# display_board.net
KiCad netlist of a schematic drawn in EAGLE
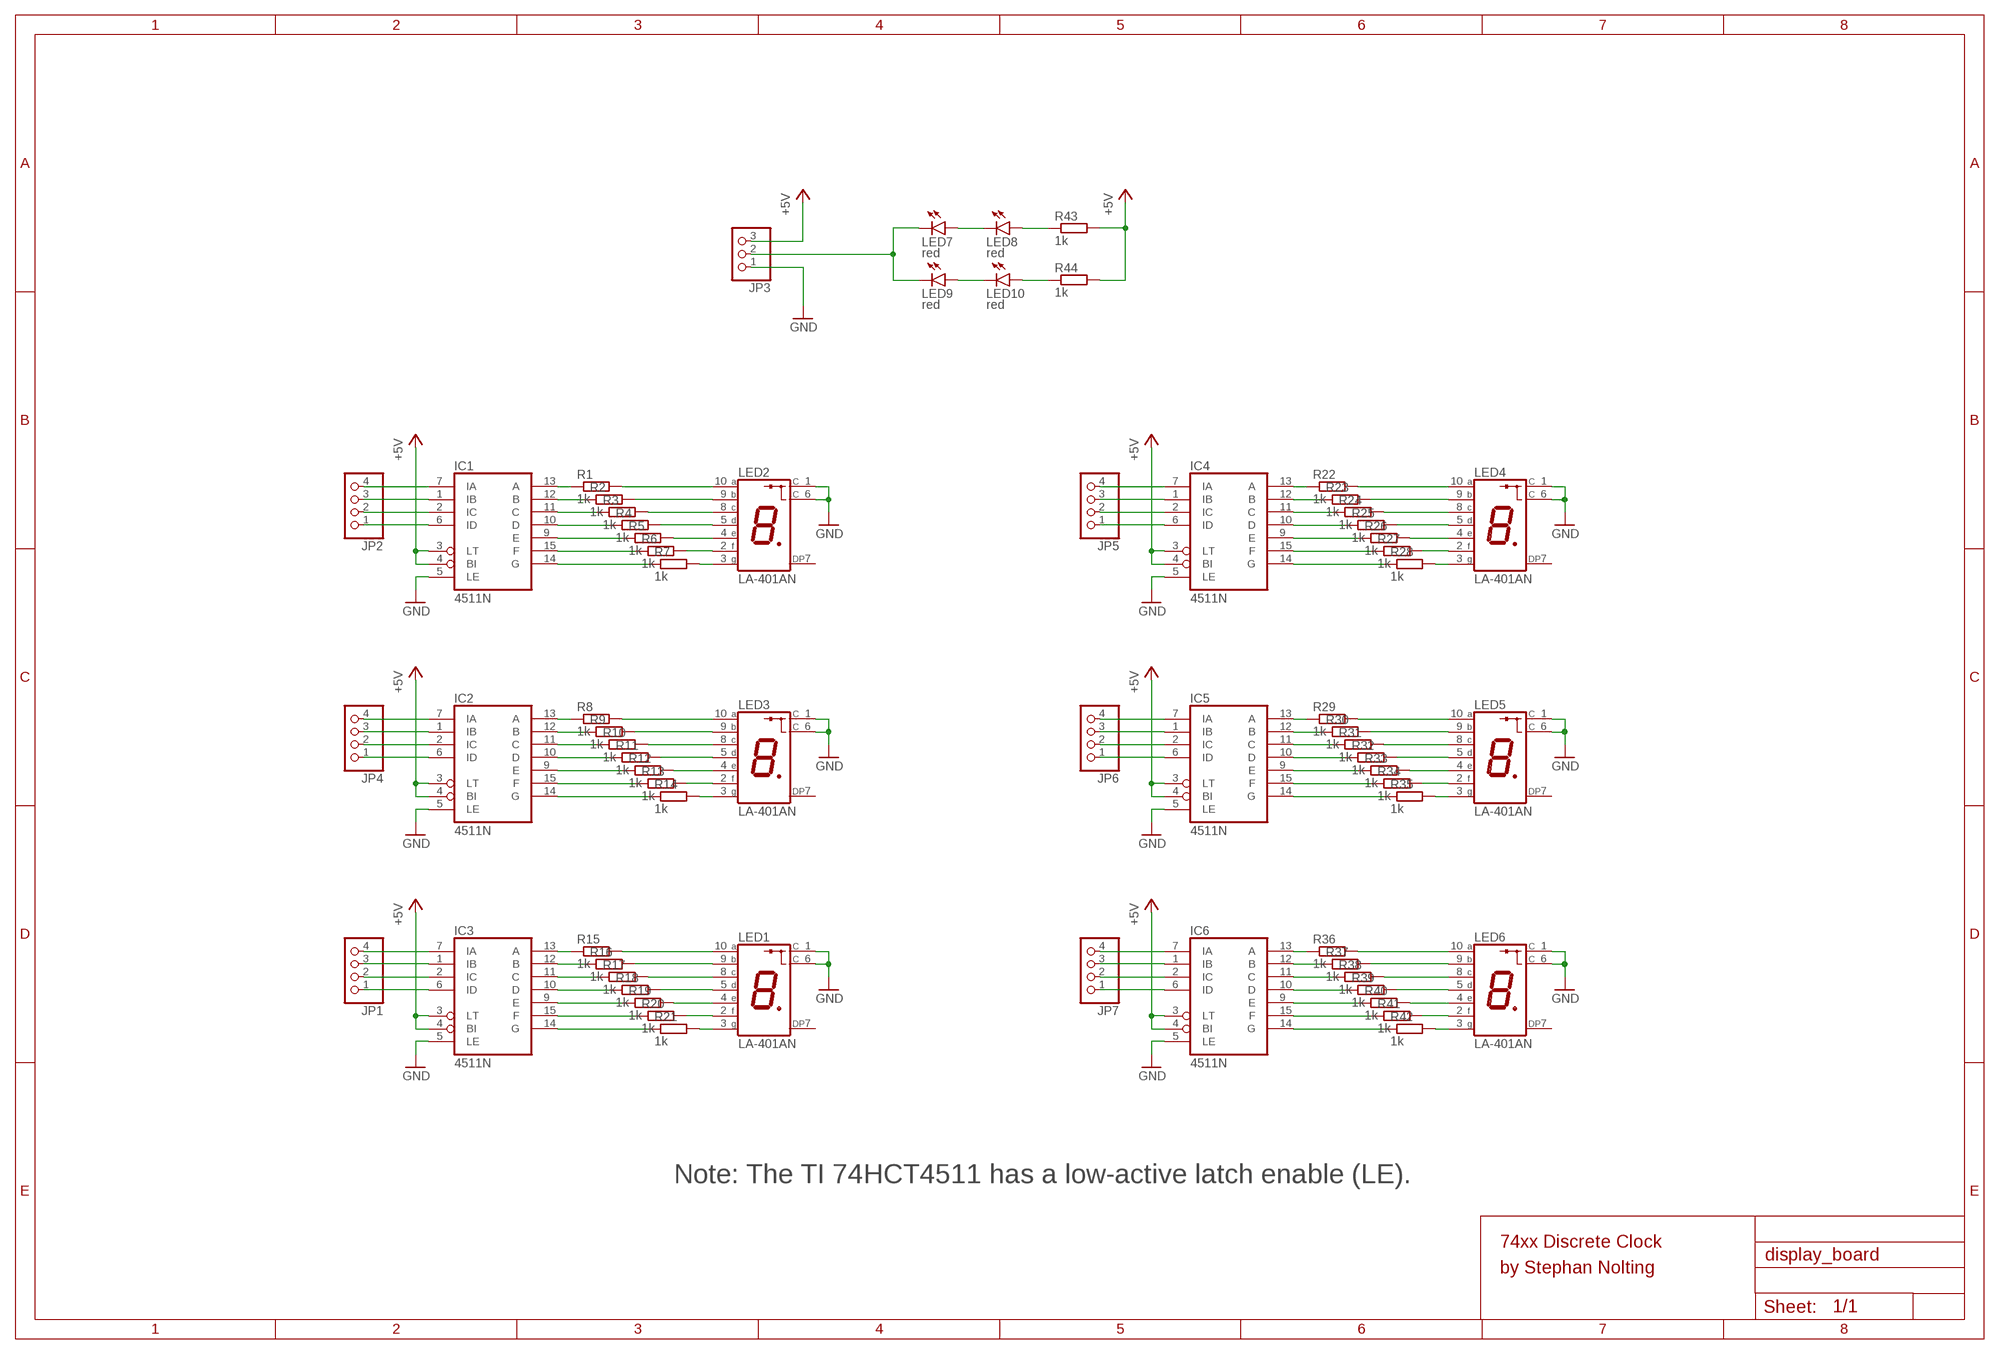
[diagram p0: schematic, sheet 1]

(export (version "E")
  (design (tool "Eeschema 10.0.6"))
  (components
    (comp (ref "IC1")
      (value "4511N")
      (footprint "eagle-import:DIL16")
      (libsource (lib "eagle-import") (part "4511N"))
    )
    (comp (ref "IC2")
      (value "4511N")
      (footprint "eagle-import:DIL16")
      (libsource (lib "eagle-import") (part "4511N"))
    )
    (comp (ref "IC3")
      (value "4511N")
      (footprint "eagle-import:DIL16")
      (libsource (lib "eagle-import") (part "4511N"))
    )
    (comp (ref "IC4")
      (value "4511N")
      (footprint "eagle-import:DIL16")
      (libsource (lib "eagle-import") (part "4511N"))
    )
    (comp (ref "IC5")
      (value "4511N")
      (footprint "eagle-import:DIL16")
      (libsource (lib "eagle-import") (part "4511N"))
    )
    (comp (ref "IC6")
      (value "4511N")
      (footprint "eagle-import:DIL16")
      (libsource (lib "eagle-import") (part "4511N"))
    )
    (comp (ref "JP1")
      (value "PINHD-1X4")
      (footprint "eagle-import:1X04")
      (libsource (lib "eagle-import") (part "PINHD-1X4"))
    )
    (comp (ref "JP2")
      (value "PINHD-1X4")
      (footprint "eagle-import:1X04")
      (libsource (lib "eagle-import") (part "PINHD-1X4"))
    )
    (comp (ref "JP3")
      (value "PINHD-1X3")
      (footprint "eagle-import:1X03")
      (libsource (lib "eagle-import") (part "PINHD-1X3"))
    )
    (comp (ref "JP4")
      (value "PINHD-1X4")
      (footprint "eagle-import:1X04")
      (libsource (lib "eagle-import") (part "PINHD-1X4"))
    )
    (comp (ref "JP5")
      (value "PINHD-1X4")
      (footprint "eagle-import:1X04")
      (libsource (lib "eagle-import") (part "PINHD-1X4"))
    )
    (comp (ref "JP6")
      (value "PINHD-1X4")
      (footprint "eagle-import:1X04")
      (libsource (lib "eagle-import") (part "PINHD-1X4"))
    )
    (comp (ref "JP7")
      (value "PINHD-1X4")
      (footprint "eagle-import:1X04")
      (libsource (lib "eagle-import") (part "PINHD-1X4"))
    )
    (comp (ref "LED1")
      (value "LA-401AN")
      (footprint "eagle-import:LA-401")
      (libsource (lib "eagle-import") (part "LA-401NA"))
    )
    (comp (ref "LED2")
      (value "LA-401AN")
      (footprint "eagle-import:LA-401")
      (libsource (lib "eagle-import") (part "LA-401NA"))
    )
    (comp (ref "LED3")
      (value "LA-401AN")
      (footprint "eagle-import:LA-401")
      (libsource (lib "eagle-import") (part "LA-401NA"))
    )
    (comp (ref "LED4")
      (value "LA-401AN")
      (footprint "eagle-import:LA-401")
      (libsource (lib "eagle-import") (part "LA-401NA"))
    )
    (comp (ref "LED5")
      (value "LA-401AN")
      (footprint "eagle-import:LA-401")
      (libsource (lib "eagle-import") (part "LA-401NA"))
    )
    (comp (ref "LED6")
      (value "LA-401AN")
      (footprint "eagle-import:LA-401")
      (libsource (lib "eagle-import") (part "LA-401NA"))
    )
    (comp (ref "LED7")
      (value "red")
      (footprint "eagle-import:LED3MM")
      (libsource (lib "eagle-import") (part "LED3MM"))
    )
    (comp (ref "LED8")
      (value "red")
      (footprint "eagle-import:LED3MM")
      (libsource (lib "eagle-import") (part "LED3MM"))
    )
    (comp (ref "LED9")
      (value "red")
      (footprint "eagle-import:LED3MM")
      (libsource (lib "eagle-import") (part "LED3MM"))
    )
    (comp (ref "LED10")
      (value "red")
      (footprint "eagle-import:LED3MM")
      (libsource (lib "eagle-import") (part "LED3MM"))
    )
    (comp (ref "R1")
      (value "1k")
      (footprint "eagle-import:0204_7")
      (libsource (lib "eagle-import") (part "R-EU_0204/7"))
    )
    (comp (ref "R2")
      (value "1k")
      (footprint "eagle-import:0204_7")
      (libsource (lib "eagle-import") (part "R-EU_0204/7"))
    )
    (comp (ref "R3")
      (value "1k")
      (footprint "eagle-import:0204_7")
      (libsource (lib "eagle-import") (part "R-EU_0204/7"))
    )
    (comp (ref "R4")
      (value "1k")
      (footprint "eagle-import:0204_7")
      (libsource (lib "eagle-import") (part "R-EU_0204/7"))
    )
    (comp (ref "R5")
      (value "1k")
      (footprint "eagle-import:0204_7")
      (libsource (lib "eagle-import") (part "R-EU_0204/7"))
    )
    (comp (ref "R6")
      (value "1k")
      (footprint "eagle-import:0204_7")
      (libsource (lib "eagle-import") (part "R-EU_0204/7"))
    )
    (comp (ref "R7")
      (value "1k")
      (footprint "eagle-import:0204_7")
      (libsource (lib "eagle-import") (part "R-EU_0204/7"))
    )
    (comp (ref "R8")
      (value "1k")
      (footprint "eagle-import:0204_7")
      (libsource (lib "eagle-import") (part "R-EU_0204/7"))
    )
    (comp (ref "R9")
      (value "1k")
      (footprint "eagle-import:0204_7")
      (libsource (lib "eagle-import") (part "R-EU_0204/7"))
    )
    (comp (ref "R10")
      (value "1k")
      (footprint "eagle-import:0204_7")
      (libsource (lib "eagle-import") (part "R-EU_0204/7"))
    )
    (comp (ref "R11")
      (value "1k")
      (footprint "eagle-import:0204_7")
      (libsource (lib "eagle-import") (part "R-EU_0204/7"))
    )
    (comp (ref "R12")
      (value "1k")
      (footprint "eagle-import:0204_7")
      (libsource (lib "eagle-import") (part "R-EU_0204/7"))
    )
    (comp (ref "R13")
      (value "1k")
      (footprint "eagle-import:0204_7")
      (libsource (lib "eagle-import") (part "R-EU_0204/7"))
    )
    (comp (ref "R14")
      (value "1k")
      (footprint "eagle-import:0204_7")
      (libsource (lib "eagle-import") (part "R-EU_0204/7"))
    )
    (comp (ref "R15")
      (value "1k")
      (footprint "eagle-import:0204_7")
      (libsource (lib "eagle-import") (part "R-EU_0204/7"))
    )
    (comp (ref "R16")
      (value "1k")
      (footprint "eagle-import:0204_7")
      (libsource (lib "eagle-import") (part "R-EU_0204/7"))
    )
    (comp (ref "R17")
      (value "1k")
      (footprint "eagle-import:0204_7")
      (libsource (lib "eagle-import") (part "R-EU_0204/7"))
    )
    (comp (ref "R18")
      (value "1k")
      (footprint "eagle-import:0204_7")
      (libsource (lib "eagle-import") (part "R-EU_0204/7"))
    )
    (comp (ref "R19")
      (value "1k")
      (footprint "eagle-import:0204_7")
      (libsource (lib "eagle-import") (part "R-EU_0204/7"))
    )
    (comp (ref "R20")
      (value "1k")
      (footprint "eagle-import:0204_7")
      (libsource (lib "eagle-import") (part "R-EU_0204/7"))
    )
    (comp (ref "R21")
      (value "1k")
      (footprint "eagle-import:0204_7")
      (libsource (lib "eagle-import") (part "R-EU_0204/7"))
    )
    (comp (ref "R22")
      (value "1k")
      (footprint "eagle-import:0204_7")
      (libsource (lib "eagle-import") (part "R-EU_0204/7"))
    )
    (comp (ref "R23")
      (value "1k")
      (footprint "eagle-import:0204_7")
      (libsource (lib "eagle-import") (part "R-EU_0204/7"))
    )
    (comp (ref "R24")
      (value "1k")
      (footprint "eagle-import:0204_7")
      (libsource (lib "eagle-import") (part "R-EU_0204/7"))
    )
    (comp (ref "R25")
      (value "1k")
      (footprint "eagle-import:0204_7")
      (libsource (lib "eagle-import") (part "R-EU_0204/7"))
    )
    (comp (ref "R26")
      (value "1k")
      (footprint "eagle-import:0204_7")
      (libsource (lib "eagle-import") (part "R-EU_0204/7"))
    )
    (comp (ref "R27")
      (value "1k")
      (footprint "eagle-import:0204_7")
      (libsource (lib "eagle-import") (part "R-EU_0204/7"))
    )
    (comp (ref "R28")
      (value "1k")
      (footprint "eagle-import:0204_7")
      (libsource (lib "eagle-import") (part "R-EU_0204/7"))
    )
    (comp (ref "R29")
      (value "1k")
      (footprint "eagle-import:0204_7")
      (libsource (lib "eagle-import") (part "R-EU_0204/7"))
    )
    (comp (ref "R30")
      (value "1k")
      (footprint "eagle-import:0204_7")
      (libsource (lib "eagle-import") (part "R-EU_0204/7"))
    )
    (comp (ref "R31")
      (value "1k")
      (footprint "eagle-import:0204_7")
      (libsource (lib "eagle-import") (part "R-EU_0204/7"))
    )
    (comp (ref "R32")
      (value "1k")
      (footprint "eagle-import:0204_7")
      (libsource (lib "eagle-import") (part "R-EU_0204/7"))
    )
    (comp (ref "R33")
      (value "1k")
      (footprint "eagle-import:0204_7")
      (libsource (lib "eagle-import") (part "R-EU_0204/7"))
    )
    (comp (ref "R34")
      (value "1k")
      (footprint "eagle-import:0204_7")
      (libsource (lib "eagle-import") (part "R-EU_0204/7"))
    )
    (comp (ref "R35")
      (value "1k")
      (footprint "eagle-import:0204_7")
      (libsource (lib "eagle-import") (part "R-EU_0204/7"))
    )
    (comp (ref "R36")
      (value "1k")
      (footprint "eagle-import:0204_7")
      (libsource (lib "eagle-import") (part "R-EU_0204/7"))
    )
    (comp (ref "R37")
      (value "1k")
      (footprint "eagle-import:0204_7")
      (libsource (lib "eagle-import") (part "R-EU_0204/7"))
    )
    (comp (ref "R38")
      (value "1k")
      (footprint "eagle-import:0204_7")
      (libsource (lib "eagle-import") (part "R-EU_0204/7"))
    )
    (comp (ref "R39")
      (value "1k")
      (footprint "eagle-import:0204_7")
      (libsource (lib "eagle-import") (part "R-EU_0204/7"))
    )
    (comp (ref "R40")
      (value "1k")
      (footprint "eagle-import:0204_7")
      (libsource (lib "eagle-import") (part "R-EU_0204/7"))
    )
    (comp (ref "R41")
      (value "1k")
      (footprint "eagle-import:0204_7")
      (libsource (lib "eagle-import") (part "R-EU_0204/7"))
    )
    (comp (ref "R42")
      (value "1k")
      (footprint "eagle-import:0204_7")
      (libsource (lib "eagle-import") (part "R-EU_0204/7"))
    )
    (comp (ref "R43")
      (value "1k")
      (footprint "eagle-import:0204_7")
      (libsource (lib "eagle-import") (part "R-EU_0204/7"))
    )
    (comp (ref "R44")
      (value "1k")
      (footprint "eagle-import:0204_7")
      (libsource (lib "eagle-import") (part "R-EU_0204/7"))
    )
  )
  (nets
    (net (code "1") (name "+5V") (class "Default")
      (node (ref "IC1") (pin "3") (pinfunction "LT_3") (pintype "input"))
      (node (ref "IC1") (pin "4") (pinfunction "BI_4") (pintype "input"))
      (node (ref "IC2") (pin "3") (pinfunction "LT_3") (pintype "input"))
      (node (ref "IC2") (pin "4") (pinfunction "BI_4") (pintype "input"))
      (node (ref "IC3") (pin "3") (pinfunction "LT_3") (pintype "input"))
      (node (ref "IC3") (pin "4") (pinfunction "BI_4") (pintype "input"))
      (node (ref "IC4") (pin "3") (pinfunction "LT_3") (pintype "input"))
      (node (ref "IC4") (pin "4") (pinfunction "BI_4") (pintype "input"))
      (node (ref "IC5") (pin "3") (pinfunction "LT_3") (pintype "input"))
      (node (ref "IC5") (pin "4") (pinfunction "BI_4") (pintype "input"))
      (node (ref "IC6") (pin "3") (pinfunction "LT_3") (pintype "input"))
      (node (ref "IC6") (pin "4") (pinfunction "BI_4") (pintype "input"))
      (node (ref "JP3") (pin "3") (pinfunction "3_3") (pintype "passive"))
      (node (ref "R43") (pin "2") (pinfunction "2_2") (pintype "passive"))
      (node (ref "R44") (pin "2") (pinfunction "2_2") (pintype "passive"))
    )
    (net (code "2") (name "GND") (class "Default")
      (node (ref "IC1") (pin "5") (pinfunction "LE_5") (pintype "input"))
      (node (ref "IC2") (pin "5") (pinfunction "LE_5") (pintype "input"))
      (node (ref "IC3") (pin "5") (pinfunction "LE_5") (pintype "input"))
      (node (ref "IC4") (pin "5") (pinfunction "LE_5") (pintype "input"))
      (node (ref "IC5") (pin "5") (pinfunction "LE_5") (pintype "input"))
      (node (ref "IC6") (pin "5") (pinfunction "LE_5") (pintype "input"))
      (node (ref "JP3") (pin "1") (pinfunction "1_1") (pintype "passive"))
      (node (ref "LED1") (pin "1") (pinfunction "C_1") (pintype "passive"))
      (node (ref "LED1") (pin "6") (pinfunction "C_6") (pintype "passive"))
      (node (ref "LED2") (pin "1") (pinfunction "C_1") (pintype "passive"))
      (node (ref "LED2") (pin "6") (pinfunction "C_6") (pintype "passive"))
      (node (ref "LED3") (pin "1") (pinfunction "C_1") (pintype "passive"))
      (node (ref "LED3") (pin "6") (pinfunction "C_6") (pintype "passive"))
      (node (ref "LED4") (pin "1") (pinfunction "C_1") (pintype "passive"))
      (node (ref "LED4") (pin "6") (pinfunction "C_6") (pintype "passive"))
      (node (ref "LED5") (pin "1") (pinfunction "C_1") (pintype "passive"))
      (node (ref "LED5") (pin "6") (pinfunction "C_6") (pintype "passive"))
      (node (ref "LED6") (pin "1") (pinfunction "C_1") (pintype "passive"))
      (node (ref "LED6") (pin "6") (pinfunction "C_6") (pintype "passive"))
    )
    (net (code "3") (name "Net-(IC1A-A)") (class "Default")
      (node (ref "IC1") (pin "13") (pinfunction "A_13") (pintype "output"))
      (node (ref "R1") (pin "1") (pinfunction "1_1") (pintype "passive"))
    )
    (net (code "4") (name "Net-(IC1A-B)") (class "Default")
      (node (ref "IC1") (pin "12") (pinfunction "B_12") (pintype "output"))
      (node (ref "R2") (pin "1") (pinfunction "1_1") (pintype "passive"))
    )
    (net (code "5") (name "Net-(IC1A-C)") (class "Default")
      (node (ref "IC1") (pin "11") (pinfunction "C_11") (pintype "output"))
      (node (ref "R3") (pin "1") (pinfunction "1_1") (pintype "passive"))
    )
    (net (code "6") (name "Net-(IC1A-D)") (class "Default")
      (node (ref "IC1") (pin "10") (pinfunction "D_10") (pintype "output"))
      (node (ref "R4") (pin "1") (pinfunction "1_1") (pintype "passive"))
    )
    (net (code "7") (name "Net-(IC1A-E)") (class "Default")
      (node (ref "IC1") (pin "9") (pinfunction "E_9") (pintype "output"))
      (node (ref "R5") (pin "1") (pinfunction "1_1") (pintype "passive"))
    )
    (net (code "8") (name "Net-(IC1A-F)") (class "Default")
      (node (ref "IC1") (pin "15") (pinfunction "F_15") (pintype "output"))
      (node (ref "R6") (pin "1") (pinfunction "1_1") (pintype "passive"))
    )
    (net (code "9") (name "Net-(IC1A-G)") (class "Default")
      (node (ref "IC1") (pin "14") (pinfunction "G_14") (pintype "output"))
      (node (ref "R7") (pin "1") (pinfunction "1_1") (pintype "passive"))
    )
    (net (code "10") (name "Net-(IC1A-IA)") (class "Default")
      (node (ref "IC1") (pin "7") (pinfunction "IA_7") (pintype "input"))
      (node (ref "JP2") (pin "4") (pinfunction "4_4") (pintype "passive"))
    )
    (net (code "11") (name "Net-(IC1A-IB)") (class "Default")
      (node (ref "IC1") (pin "1") (pinfunction "IB_1") (pintype "input"))
      (node (ref "JP2") (pin "3") (pinfunction "3_3") (pintype "passive"))
    )
    (net (code "12") (name "Net-(IC1A-IC)") (class "Default")
      (node (ref "IC1") (pin "2") (pinfunction "IC_2") (pintype "input"))
      (node (ref "JP2") (pin "2") (pinfunction "2_2") (pintype "passive"))
    )
    (net (code "13") (name "Net-(IC1A-ID)") (class "Default")
      (node (ref "IC1") (pin "6") (pinfunction "ID_6") (pintype "input"))
      (node (ref "JP2") (pin "1") (pinfunction "1_1") (pintype "passive"))
    )
    (net (code "14") (name "Net-(IC2A-A)") (class "Default")
      (node (ref "IC2") (pin "13") (pinfunction "A_13") (pintype "output"))
      (node (ref "R8") (pin "1") (pinfunction "1_1") (pintype "passive"))
    )
    (net (code "15") (name "Net-(IC2A-B)") (class "Default")
      (node (ref "IC2") (pin "12") (pinfunction "B_12") (pintype "output"))
      (node (ref "R9") (pin "1") (pinfunction "1_1") (pintype "passive"))
    )
    (net (code "16") (name "Net-(IC2A-C)") (class "Default")
      (node (ref "IC2") (pin "11") (pinfunction "C_11") (pintype "output"))
      (node (ref "R10") (pin "1") (pinfunction "1_1") (pintype "passive"))
    )
    (net (code "17") (name "Net-(IC2A-D)") (class "Default")
      (node (ref "IC2") (pin "10") (pinfunction "D_10") (pintype "output"))
      (node (ref "R11") (pin "1") (pinfunction "1_1") (pintype "passive"))
    )
    (net (code "18") (name "Net-(IC2A-E)") (class "Default")
      (node (ref "IC2") (pin "9") (pinfunction "E_9") (pintype "output"))
      (node (ref "R12") (pin "1") (pinfunction "1_1") (pintype "passive"))
    )
    (net (code "19") (name "Net-(IC2A-F)") (class "Default")
      (node (ref "IC2") (pin "15") (pinfunction "F_15") (pintype "output"))
      (node (ref "R13") (pin "1") (pinfunction "1_1") (pintype "passive"))
    )
    (net (code "20") (name "Net-(IC2A-G)") (class "Default")
      (node (ref "IC2") (pin "14") (pinfunction "G_14") (pintype "output"))
      (node (ref "R14") (pin "1") (pinfunction "1_1") (pintype "passive"))
    )
    (net (code "21") (name "Net-(IC2A-IA)") (class "Default")
      (node (ref "IC2") (pin "7") (pinfunction "IA_7") (pintype "input"))
      (node (ref "JP4") (pin "4") (pinfunction "4_4") (pintype "passive"))
    )
    (net (code "22") (name "Net-(IC2A-IB)") (class "Default")
      (node (ref "IC2") (pin "1") (pinfunction "IB_1") (pintype "input"))
      (node (ref "JP4") (pin "3") (pinfunction "3_3") (pintype "passive"))
    )
    (net (code "23") (name "Net-(IC2A-IC)") (class "Default")
      (node (ref "IC2") (pin "2") (pinfunction "IC_2") (pintype "input"))
      (node (ref "JP4") (pin "2") (pinfunction "2_2") (pintype "passive"))
    )
    (net (code "24") (name "Net-(IC2A-ID)") (class "Default")
      (node (ref "IC2") (pin "6") (pinfunction "ID_6") (pintype "input"))
      (node (ref "JP4") (pin "1") (pinfunction "1_1") (pintype "passive"))
    )
    (net (code "25") (name "Net-(IC3A-A)") (class "Default")
      (node (ref "IC3") (pin "13") (pinfunction "A_13") (pintype "output"))
      (node (ref "R15") (pin "1") (pinfunction "1_1") (pintype "passive"))
    )
    (net (code "26") (name "Net-(IC3A-B)") (class "Default")
      (node (ref "IC3") (pin "12") (pinfunction "B_12") (pintype "output"))
      (node (ref "R16") (pin "1") (pinfunction "1_1") (pintype "passive"))
    )
    (net (code "27") (name "Net-(IC3A-C)") (class "Default")
      (node (ref "IC3") (pin "11") (pinfunction "C_11") (pintype "output"))
      (node (ref "R17") (pin "1") (pinfunction "1_1") (pintype "passive"))
    )
    (net (code "28") (name "Net-(IC3A-D)") (class "Default")
      (node (ref "IC3") (pin "10") (pinfunction "D_10") (pintype "output"))
      (node (ref "R18") (pin "1") (pinfunction "1_1") (pintype "passive"))
    )
    (net (code "29") (name "Net-(IC3A-E)") (class "Default")
      (node (ref "IC3") (pin "9") (pinfunction "E_9") (pintype "output"))
      (node (ref "R19") (pin "1") (pinfunction "1_1") (pintype "passive"))
    )
    (net (code "30") (name "Net-(IC3A-F)") (class "Default")
      (node (ref "IC3") (pin "15") (pinfunction "F_15") (pintype "output"))
      (node (ref "R20") (pin "1") (pinfunction "1_1") (pintype "passive"))
    )
    (net (code "31") (name "Net-(IC3A-G)") (class "Default")
      (node (ref "IC3") (pin "14") (pinfunction "G_14") (pintype "output"))
      (node (ref "R21") (pin "1") (pinfunction "1_1") (pintype "passive"))
    )
    (net (code "32") (name "Net-(IC3A-IA)") (class "Default")
      (node (ref "IC3") (pin "7") (pinfunction "IA_7") (pintype "input"))
      (node (ref "JP1") (pin "4") (pinfunction "4_4") (pintype "passive"))
    )
    (net (code "33") (name "Net-(IC3A-IB)") (class "Default")
      (node (ref "IC3") (pin "1") (pinfunction "IB_1") (pintype "input"))
      (node (ref "JP1") (pin "3") (pinfunction "3_3") (pintype "passive"))
    )
    (net (code "34") (name "Net-(IC3A-IC)") (class "Default")
      (node (ref "IC3") (pin "2") (pinfunction "IC_2") (pintype "input"))
      (node (ref "JP1") (pin "2") (pinfunction "2_2") (pintype "passive"))
    )
    (net (code "35") (name "Net-(IC3A-ID)") (class "Default")
      (node (ref "IC3") (pin "6") (pinfunction "ID_6") (pintype "input"))
      (node (ref "JP1") (pin "1") (pinfunction "1_1") (pintype "passive"))
    )
    (net (code "36") (name "Net-(IC4A-A)") (class "Default")
      (node (ref "IC4") (pin "13") (pinfunction "A_13") (pintype "output"))
      (node (ref "R22") (pin "1") (pinfunction "1_1") (pintype "passive"))
    )
    (net (code "37") (name "Net-(IC4A-B)") (class "Default")
      (node (ref "IC4") (pin "12") (pinfunction "B_12") (pintype "output"))
      (node (ref "R23") (pin "1") (pinfunction "1_1") (pintype "passive"))
    )
    (net (code "38") (name "Net-(IC4A-C)") (class "Default")
      (node (ref "IC4") (pin "11") (pinfunction "C_11") (pintype "output"))
      (node (ref "R24") (pin "1") (pinfunction "1_1") (pintype "passive"))
    )
    (net (code "39") (name "Net-(IC4A-D)") (class "Default")
      (node (ref "IC4") (pin "10") (pinfunction "D_10") (pintype "output"))
      (node (ref "R25") (pin "1") (pinfunction "1_1") (pintype "passive"))
    )
    (net (code "40") (name "Net-(IC4A-E)") (class "Default")
      (node (ref "IC4") (pin "9") (pinfunction "E_9") (pintype "output"))
      (node (ref "R26") (pin "1") (pinfunction "1_1") (pintype "passive"))
    )
    (net (code "41") (name "Net-(IC4A-F)") (class "Default")
      (node (ref "IC4") (pin "15") (pinfunction "F_15") (pintype "output"))
      (node (ref "R27") (pin "1") (pinfunction "1_1") (pintype "passive"))
    )
    (net (code "42") (name "Net-(IC4A-G)") (class "Default")
      (node (ref "IC4") (pin "14") (pinfunction "G_14") (pintype "output"))
      (node (ref "R28") (pin "1") (pinfunction "1_1") (pintype "passive"))
    )
    (net (code "43") (name "Net-(IC4A-IA)") (class "Default")
      (node (ref "IC4") (pin "7") (pinfunction "IA_7") (pintype "input"))
      (node (ref "JP5") (pin "4") (pinfunction "4_4") (pintype "passive"))
    )
    (net (code "44") (name "Net-(IC4A-IB)") (class "Default")
      (node (ref "IC4") (pin "1") (pinfunction "IB_1") (pintype "input"))
      (node (ref "JP5") (pin "3") (pinfunction "3_3") (pintype "passive"))
    )
    (net (code "45") (name "Net-(IC4A-IC)") (class "Default")
      (node (ref "IC4") (pin "2") (pinfunction "IC_2") (pintype "input"))
      (node (ref "JP5") (pin "2") (pinfunction "2_2") (pintype "passive"))
    )
    (net (code "46") (name "Net-(IC4A-ID)") (class "Default")
      (node (ref "IC4") (pin "6") (pinfunction "ID_6") (pintype "input"))
      (node (ref "JP5") (pin "1") (pinfunction "1_1") (pintype "passive"))
    )
    (net (code "47") (name "Net-(IC5A-A)") (class "Default")
      (node (ref "IC5") (pin "13") (pinfunction "A_13") (pintype "output"))
      (node (ref "R29") (pin "1") (pinfunction "1_1") (pintype "passive"))
    )
    (net (code "48") (name "Net-(IC5A-B)") (class "Default")
      (node (ref "IC5") (pin "12") (pinfunction "B_12") (pintype "output"))
      (node (ref "R30") (pin "1") (pinfunction "1_1") (pintype "passive"))
    )
    (net (code "49") (name "Net-(IC5A-C)") (class "Default")
      (node (ref "IC5") (pin "11") (pinfunction "C_11") (pintype "output"))
      (node (ref "R31") (pin "1") (pinfunction "1_1") (pintype "passive"))
    )
    (net (code "50") (name "Net-(IC5A-D)") (class "Default")
      (node (ref "IC5") (pin "10") (pinfunction "D_10") (pintype "output"))
      (node (ref "R32") (pin "1") (pinfunction "1_1") (pintype "passive"))
    )
    (net (code "51") (name "Net-(IC5A-E)") (class "Default")
      (node (ref "IC5") (pin "9") (pinfunction "E_9") (pintype "output"))
      (node (ref "R33") (pin "1") (pinfunction "1_1") (pintype "passive"))
    )
    (net (code "52") (name "Net-(IC5A-F)") (class "Default")
      (node (ref "IC5") (pin "15") (pinfunction "F_15") (pintype "output"))
      (node (ref "R34") (pin "1") (pinfunction "1_1") (pintype "passive"))
    )
    (net (code "53") (name "Net-(IC5A-G)") (class "Default")
      (node (ref "IC5") (pin "14") (pinfunction "G_14") (pintype "output"))
      (node (ref "R35") (pin "1") (pinfunction "1_1") (pintype "passive"))
    )
    (net (code "54") (name "Net-(IC5A-IA)") (class "Default")
      (node (ref "IC5") (pin "7") (pinfunction "IA_7") (pintype "input"))
      (node (ref "JP6") (pin "4") (pinfunction "4_4") (pintype "passive"))
    )
    (net (code "55") (name "Net-(IC5A-IB)") (class "Default")
      (node (ref "IC5") (pin "1") (pinfunction "IB_1") (pintype "input"))
      (node (ref "JP6") (pin "3") (pinfunction "3_3") (pintype "passive"))
    )
    (net (code "56") (name "Net-(IC5A-IC)") (class "Default")
      (node (ref "IC5") (pin "2") (pinfunction "IC_2") (pintype "input"))
      (node (ref "JP6") (pin "2") (pinfunction "2_2") (pintype "passive"))
    )
    (net (code "57") (name "Net-(IC5A-ID)") (class "Default")
      (node (ref "IC5") (pin "6") (pinfunction "ID_6") (pintype "input"))
      (node (ref "JP6") (pin "1") (pinfunction "1_1") (pintype "passive"))
    )
    (net (code "58") (name "Net-(IC6A-A)") (class "Default")
      (node (ref "IC6") (pin "13") (pinfunction "A_13") (pintype "output"))
      (node (ref "R36") (pin "1") (pinfunction "1_1") (pintype "passive"))
    )
    (net (code "59") (name "Net-(IC6A-B)") (class "Default")
      (node (ref "IC6") (pin "12") (pinfunction "B_12") (pintype "output"))
      (node (ref "R37") (pin "1") (pinfunction "1_1") (pintype "passive"))
    )
    (net (code "60") (name "Net-(IC6A-C)") (class "Default")
      (node (ref "IC6") (pin "11") (pinfunction "C_11") (pintype "output"))
      (node (ref "R38") (pin "1") (pinfunction "1_1") (pintype "passive"))
    )
    (net (code "61") (name "Net-(IC6A-D)") (class "Default")
      (node (ref "IC6") (pin "10") (pinfunction "D_10") (pintype "output"))
      (node (ref "R39") (pin "1") (pinfunction "1_1") (pintype "passive"))
    )
    (net (code "62") (name "Net-(IC6A-E)") (class "Default")
      (node (ref "IC6") (pin "9") (pinfunction "E_9") (pintype "output"))
      (node (ref "R40") (pin "1") (pinfunction "1_1") (pintype "passive"))
    )
    (net (code "63") (name "Net-(IC6A-F)") (class "Default")
      (node (ref "IC6") (pin "15") (pinfunction "F_15") (pintype "output"))
      (node (ref "R41") (pin "1") (pinfunction "1_1") (pintype "passive"))
    )
    (net (code "64") (name "Net-(IC6A-G)") (class "Default")
      (node (ref "IC6") (pin "14") (pinfunction "G_14") (pintype "output"))
      (node (ref "R42") (pin "1") (pinfunction "1_1") (pintype "passive"))
    )
    (net (code "65") (name "Net-(IC6A-IA)") (class "Default")
      (node (ref "IC6") (pin "7") (pinfunction "IA_7") (pintype "input"))
      (node (ref "JP7") (pin "4") (pinfunction "4_4") (pintype "passive"))
    )
    (net (code "66") (name "Net-(IC6A-IB)") (class "Default")
      (node (ref "IC6") (pin "1") (pinfunction "IB_1") (pintype "input"))
      (node (ref "JP7") (pin "3") (pinfunction "3_3") (pintype "passive"))
    )
    (net (code "67") (name "Net-(IC6A-IC)") (class "Default")
      (node (ref "IC6") (pin "2") (pinfunction "IC_2") (pintype "input"))
      (node (ref "JP7") (pin "2") (pinfunction "2_2") (pintype "passive"))
    )
    (net (code "68") (name "Net-(IC6A-ID)") (class "Default")
      (node (ref "IC6") (pin "6") (pinfunction "ID_6") (pintype "input"))
      (node (ref "JP7") (pin "1") (pinfunction "1_1") (pintype "passive"))
    )
    (net (code "69") (name "Net-(LED1-A)") (class "Default")
      (node (ref "LED1") (pin "10") (pinfunction "A_10") (pintype "passive"))
      (node (ref "R15") (pin "2") (pinfunction "2_2") (pintype "passive"))
    )
    (net (code "70") (name "Net-(LED1-B)") (class "Default")
      (node (ref "LED1") (pin "9") (pinfunction "B_9") (pintype "passive"))
      (node (ref "R16") (pin "2") (pinfunction "2_2") (pintype "passive"))
    )
    (net (code "71") (name "Net-(LED1-C-Pad8)") (class "Default")
      (node (ref "LED1") (pin "8") (pinfunction "C_8") (pintype "passive"))
      (node (ref "R17") (pin "2") (pinfunction "2_2") (pintype "passive"))
    )
    (net (code "72") (name "Net-(LED1-D)") (class "Default")
      (node (ref "LED1") (pin "5") (pinfunction "D_5") (pintype "passive"))
      (node (ref "R18") (pin "2") (pinfunction "2_2") (pintype "passive"))
    )
    (net (code "73") (name "Net-(LED1-E)") (class "Default")
      (node (ref "LED1") (pin "4") (pinfunction "E_4") (pintype "passive"))
      (node (ref "R19") (pin "2") (pinfunction "2_2") (pintype "passive"))
    )
    (net (code "74") (name "Net-(LED1-F)") (class "Default")
      (node (ref "LED1") (pin "2") (pinfunction "F_2") (pintype "passive"))
      (node (ref "R20") (pin "2") (pinfunction "2_2") (pintype "passive"))
    )
    (net (code "75") (name "Net-(LED1-G)") (class "Default")
      (node (ref "LED1") (pin "3") (pinfunction "G_3") (pintype "passive"))
      (node (ref "R21") (pin "2") (pinfunction "2_2") (pintype "passive"))
    )
    (net (code "76") (name "Net-(LED2-A)") (class "Default")
      (node (ref "LED2") (pin "10") (pinfunction "A_10") (pintype "passive"))
      (node (ref "R1") (pin "2") (pinfunction "2_2") (pintype "passive"))
    )
    (net (code "77") (name "Net-(LED2-B)") (class "Default")
      (node (ref "LED2") (pin "9") (pinfunction "B_9") (pintype "passive"))
      (node (ref "R2") (pin "2") (pinfunction "2_2") (pintype "passive"))
    )
    (net (code "78") (name "Net-(LED2-C-Pad8)") (class "Default")
      (node (ref "LED2") (pin "8") (pinfunction "C_8") (pintype "passive"))
      (node (ref "R3") (pin "2") (pinfunction "2_2") (pintype "passive"))
    )
    (net (code "79") (name "Net-(LED2-D)") (class "Default")
      (node (ref "LED2") (pin "5") (pinfunction "D_5") (pintype "passive"))
      (node (ref "R4") (pin "2") (pinfunction "2_2") (pintype "passive"))
    )
    (net (code "80") (name "Net-(LED2-E)") (class "Default")
      (node (ref "LED2") (pin "4") (pinfunction "E_4") (pintype "passive"))
      (node (ref "R5") (pin "2") (pinfunction "2_2") (pintype "passive"))
    )
    (net (code "81") (name "Net-(LED2-F)") (class "Default")
      (node (ref "LED2") (pin "2") (pinfunction "F_2") (pintype "passive"))
      (node (ref "R6") (pin "2") (pinfunction "2_2") (pintype "passive"))
    )
    (net (code "82") (name "Net-(LED2-G)") (class "Default")
      (node (ref "LED2") (pin "3") (pinfunction "G_3") (pintype "passive"))
      (node (ref "R7") (pin "2") (pinfunction "2_2") (pintype "passive"))
    )
    (net (code "83") (name "Net-(LED3-A)") (class "Default")
      (node (ref "LED3") (pin "10") (pinfunction "A_10") (pintype "passive"))
      (node (ref "R8") (pin "2") (pinfunction "2_2") (pintype "passive"))
    )
    (net (code "84") (name "Net-(LED3-B)") (class "Default")
      (node (ref "LED3") (pin "9") (pinfunction "B_9") (pintype "passive"))
      (node (ref "R9") (pin "2") (pinfunction "2_2") (pintype "passive"))
    )
    (net (code "85") (name "Net-(LED3-C-Pad8)") (class "Default")
      (node (ref "LED3") (pin "8") (pinfunction "C_8") (pintype "passive"))
      (node (ref "R10") (pin "2") (pinfunction "2_2") (pintype "passive"))
    )
    (net (code "86") (name "Net-(LED3-D)") (class "Default")
      (node (ref "LED3") (pin "5") (pinfunction "D_5") (pintype "passive"))
      (node (ref "R11") (pin "2") (pinfunction "2_2") (pintype "passive"))
    )
    (net (code "87") (name "Net-(LED3-E)") (class "Default")
      (node (ref "LED3") (pin "4") (pinfunction "E_4") (pintype "passive"))
      (node (ref "R12") (pin "2") (pinfunction "2_2") (pintype "passive"))
    )
    (net (code "88") (name "Net-(LED3-F)") (class "Default")
      (node (ref "LED3") (pin "2") (pinfunction "F_2") (pintype "passive"))
      (node (ref "R13") (pin "2") (pinfunction "2_2") (pintype "passive"))
    )
    (net (code "89") (name "Net-(LED3-G)") (class "Default")
      (node (ref "LED3") (pin "3") (pinfunction "G_3") (pintype "passive"))
      (node (ref "R14") (pin "2") (pinfunction "2_2") (pintype "passive"))
    )
    (net (code "90") (name "Net-(LED4-A)") (class "Default")
      (node (ref "LED4") (pin "10") (pinfunction "A_10") (pintype "passive"))
      (node (ref "R22") (pin "2") (pinfunction "2_2") (pintype "passive"))
    )
    (net (code "91") (name "Net-(LED4-B)") (class "Default")
      (node (ref "LED4") (pin "9") (pinfunction "B_9") (pintype "passive"))
      (node (ref "R23") (pin "2") (pinfunction "2_2") (pintype "passive"))
    )
    (net (code "92") (name "Net-(LED4-C-Pad8)") (class "Default")
      (node (ref "LED4") (pin "8") (pinfunction "C_8") (pintype "passive"))
      (node (ref "R24") (pin "2") (pinfunction "2_2") (pintype "passive"))
    )
    (net (code "93") (name "Net-(LED4-D)") (class "Default")
      (node (ref "LED4") (pin "5") (pinfunction "D_5") (pintype "passive"))
      (node (ref "R25") (pin "2") (pinfunction "2_2") (pintype "passive"))
    )
    (net (code "94") (name "Net-(LED4-E)") (class "Default")
      (node (ref "LED4") (pin "4") (pinfunction "E_4") (pintype "passive"))
      (node (ref "R26") (pin "2") (pinfunction "2_2") (pintype "passive"))
    )
    (net (code "95") (name "Net-(LED4-F)") (class "Default")
      (node (ref "LED4") (pin "2") (pinfunction "F_2") (pintype "passive"))
      (node (ref "R27") (pin "2") (pinfunction "2_2") (pintype "passive"))
    )
    (net (code "96") (name "Net-(LED4-G)") (class "Default")
      (node (ref "LED4") (pin "3") (pinfunction "G_3") (pintype "passive"))
      (node (ref "R28") (pin "2") (pinfunction "2_2") (pintype "passive"))
    )
    (net (code "97") (name "Net-(LED5-A)") (class "Default")
      (node (ref "LED5") (pin "10") (pinfunction "A_10") (pintype "passive"))
      (node (ref "R29") (pin "2") (pinfunction "2_2") (pintype "passive"))
    )
    (net (code "98") (name "Net-(LED5-B)") (class "Default")
      (node (ref "LED5") (pin "9") (pinfunction "B_9") (pintype "passive"))
      (node (ref "R30") (pin "2") (pinfunction "2_2") (pintype "passive"))
    )
    (net (code "99") (name "Net-(LED5-C-Pad8)") (class "Default")
      (node (ref "LED5") (pin "8") (pinfunction "C_8") (pintype "passive"))
      (node (ref "R31") (pin "2") (pinfunction "2_2") (pintype "passive"))
    )
    (net (code "100") (name "Net-(LED5-D)") (class "Default")
      (node (ref "LED5") (pin "5") (pinfunction "D_5") (pintype "passive"))
      (node (ref "R32") (pin "2") (pinfunction "2_2") (pintype "passive"))
    )
    (net (code "101") (name "Net-(LED5-E)") (class "Default")
      (node (ref "LED5") (pin "4") (pinfunction "E_4") (pintype "passive"))
      (node (ref "R33") (pin "2") (pinfunction "2_2") (pintype "passive"))
    )
    (net (code "102") (name "Net-(LED5-F)") (class "Default")
      (node (ref "LED5") (pin "2") (pinfunction "F_2") (pintype "passive"))
      (node (ref "R34") (pin "2") (pinfunction "2_2") (pintype "passive"))
    )
    (net (code "103") (name "Net-(LED5-G)") (class "Default")
      (node (ref "LED5") (pin "3") (pinfunction "G_3") (pintype "passive"))
      (node (ref "R35") (pin "2") (pinfunction "2_2") (pintype "passive"))
    )
    (net (code "104") (name "Net-(LED6-A)") (class "Default")
      (node (ref "LED6") (pin "10") (pinfunction "A_10") (pintype "passive"))
      (node (ref "R36") (pin "2") (pinfunction "2_2") (pintype "passive"))
    )
    (net (code "105") (name "Net-(LED6-B)") (class "Default")
      (node (ref "LED6") (pin "9") (pinfunction "B_9") (pintype "passive"))
      (node (ref "R37") (pin "2") (pinfunction "2_2") (pintype "passive"))
    )
    (net (code "106") (name "Net-(LED6-C-Pad8)") (class "Default")
      (node (ref "LED6") (pin "8") (pinfunction "C_8") (pintype "passive"))
      (node (ref "R38") (pin "2") (pinfunction "2_2") (pintype "passive"))
    )
    (net (code "107") (name "Net-(LED6-D)") (class "Default")
      (node (ref "LED6") (pin "5") (pinfunction "D_5") (pintype "passive"))
      (node (ref "R39") (pin "2") (pinfunction "2_2") (pintype "passive"))
    )
    (net (code "108") (name "Net-(LED6-E)") (class "Default")
      (node (ref "LED6") (pin "4") (pinfunction "E_4") (pintype "passive"))
      (node (ref "R40") (pin "2") (pinfunction "2_2") (pintype "passive"))
    )
    (net (code "109") (name "Net-(LED6-F)") (class "Default")
      (node (ref "LED6") (pin "2") (pinfunction "F_2") (pintype "passive"))
      (node (ref "R41") (pin "2") (pinfunction "2_2") (pintype "passive"))
    )
    (net (code "110") (name "Net-(LED6-G)") (class "Default")
      (node (ref "LED6") (pin "3") (pinfunction "G_3") (pintype "passive"))
      (node (ref "R42") (pin "2") (pinfunction "2_2") (pintype "passive"))
    )
    (net (code "111") (name "Net-(LED7-C)") (class "Default")
      (node (ref "JP3") (pin "2") (pinfunction "2_2") (pintype "passive"))
      (node (ref "LED7") (pin "K") (pinfunction "C_K") (pintype "passive"))
      (node (ref "LED9") (pin "K") (pinfunction "C_K") (pintype "passive"))
    )
    (net (code "112") (name "Net-(LED8-C)") (class "Default")
      (node (ref "LED7") (pin "A") (pinfunction "A_A") (pintype "passive"))
      (node (ref "LED8") (pin "K") (pinfunction "C_K") (pintype "passive"))
    )
    (net (code "113") (name "Net-(LED8-PadA)") (class "Default")
      (node (ref "LED8") (pin "A") (pinfunction "A_A") (pintype "passive"))
      (node (ref "R43") (pin "1") (pinfunction "1_1") (pintype "passive"))
    )
    (net (code "114") (name "Net-(LED10-C)") (class "Default")
      (node (ref "LED10") (pin "K") (pinfunction "C_K") (pintype "passive"))
      (node (ref "LED9") (pin "A") (pinfunction "A_A") (pintype "passive"))
    )
    (net (code "115") (name "Net-(LED10-PadA)") (class "Default")
      (node (ref "LED10") (pin "A") (pinfunction "A_A") (pintype "passive"))
      (node (ref "R44") (pin "1") (pinfunction "1_1") (pintype "passive"))
    )
    (net (code "116") (name "unconnected-(LED1-DP-Pad7)") (class "Default")
      (node (ref "LED1") (pin "7") (pinfunction "DP_7") (pintype "passive"))
    )
    (net (code "117") (name "unconnected-(LED2-DP-Pad7)") (class "Default")
      (node (ref "LED2") (pin "7") (pinfunction "DP_7") (pintype "passive"))
    )
    (net (code "118") (name "unconnected-(LED3-DP-Pad7)") (class "Default")
      (node (ref "LED3") (pin "7") (pinfunction "DP_7") (pintype "passive"))
    )
    (net (code "119") (name "unconnected-(LED4-DP-Pad7)") (class "Default")
      (node (ref "LED4") (pin "7") (pinfunction "DP_7") (pintype "passive"))
    )
    (net (code "120") (name "unconnected-(LED5-DP-Pad7)") (class "Default")
      (node (ref "LED5") (pin "7") (pinfunction "DP_7") (pintype "passive"))
    )
    (net (code "121") (name "unconnected-(LED6-DP-Pad7)") (class "Default")
      (node (ref "LED6") (pin "7") (pinfunction "DP_7") (pintype "passive"))
    )
  )
)
